# OSHWA_Badges_7.net
KiCad netlist of a schematic drawn in EAGLE
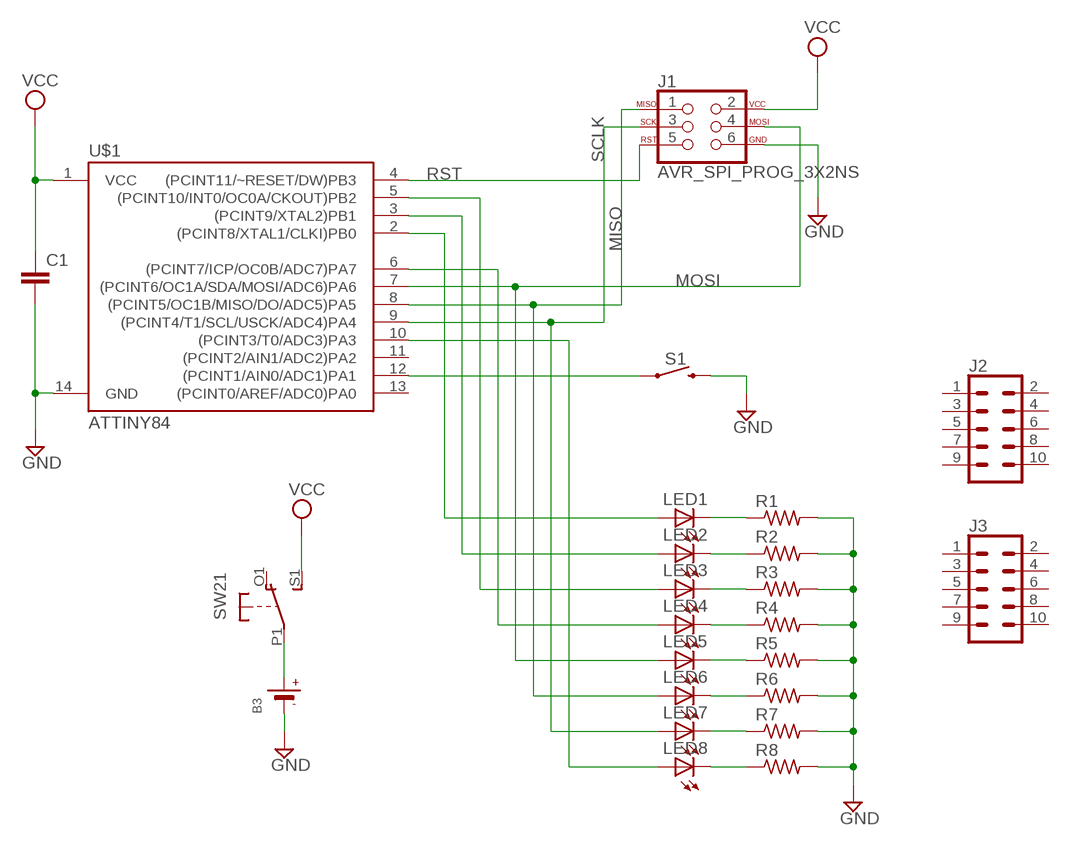
[diagram p0: schematic, sheet 1]

(export (version "E")
  (design (tool "Eeschema 10.0.6"))
  (components
    (comp (ref "B3")
      (value "BATTERYCR2032_BAT-HLD-001")
      (footprint "eagle-import:CR2032_SMT_BAT-HLD-001")
      (libsource (lib "eagle-import") (part "BATTERYCR2032_BAT-HLD-001"))
    )
    (comp (ref "C1")
      (value "C-EUC0805K")
      (footprint "eagle-import:C0805K")
      (libsource (lib "eagle-import") (part "C-EUC0805K"))
    )
    (comp (ref "J1")
      (value "AVR_SPI_PROG_3X2NS")
      (footprint "eagle-import:2X3-NS")
      (libsource (lib "eagle-import") (part "AVR_SPI_PROG_3X2NS"))
    )
    (comp (ref "J2")
      (value "CONN_05X2NO_SILK")
      (footprint "eagle-import:2X5_NOSILK")
      (libsource (lib "eagle-import") (part "CONN_05X2NO_SILK"))
    )
    (comp (ref "J3")
      (value "CONN_05X2NO_SILK")
      (footprint "eagle-import:2X5_NOSILK")
      (libsource (lib "eagle-import") (part "CONN_05X2NO_SILK"))
    )
    (comp (ref "LED1")
      (value "LEDCHIPLED_0805")
      (footprint "eagle-import:CHIPLED_0805")
      (libsource (lib "eagle-import") (part "LEDCHIPLED_0805"))
    )
    (comp (ref "LED2")
      (value "LEDCHIPLED_0805")
      (footprint "eagle-import:CHIPLED_0805")
      (libsource (lib "eagle-import") (part "LEDCHIPLED_0805"))
    )
    (comp (ref "LED3")
      (value "LEDCHIPLED_0805")
      (footprint "eagle-import:CHIPLED_0805")
      (libsource (lib "eagle-import") (part "LEDCHIPLED_0805"))
    )
    (comp (ref "LED4")
      (value "LEDCHIPLED_0805")
      (footprint "eagle-import:CHIPLED_0805")
      (libsource (lib "eagle-import") (part "LEDCHIPLED_0805"))
    )
    (comp (ref "LED5")
      (value "LEDCHIPLED_0805")
      (footprint "eagle-import:CHIPLED_0805")
      (libsource (lib "eagle-import") (part "LEDCHIPLED_0805"))
    )
    (comp (ref "LED6")
      (value "LEDCHIPLED_0805")
      (footprint "eagle-import:CHIPLED_0805")
      (libsource (lib "eagle-import") (part "LEDCHIPLED_0805"))
    )
    (comp (ref "LED7")
      (value "LEDCHIPLED_0805")
      (footprint "eagle-import:CHIPLED_0805")
      (libsource (lib "eagle-import") (part "LEDCHIPLED_0805"))
    )
    (comp (ref "LED8")
      (value "LEDCHIPLED_0805")
      (footprint "eagle-import:CHIPLED_0805")
      (libsource (lib "eagle-import") (part "LEDCHIPLED_0805"))
    )
    (comp (ref "R1")
      (value "R-US_M0805")
      (footprint "eagle-import:M0805")
      (libsource (lib "eagle-import") (part "R-US_M0805"))
    )
    (comp (ref "R2")
      (value "R-US_M0805")
      (footprint "eagle-import:M0805")
      (libsource (lib "eagle-import") (part "R-US_M0805"))
    )
    (comp (ref "R3")
      (value "R-US_M0805")
      (footprint "eagle-import:M0805")
      (libsource (lib "eagle-import") (part "R-US_M0805"))
    )
    (comp (ref "R4")
      (value "R-US_M0805")
      (footprint "eagle-import:M0805")
      (libsource (lib "eagle-import") (part "R-US_M0805"))
    )
    (comp (ref "R5")
      (value "R-US_M0805")
      (footprint "eagle-import:M0805")
      (libsource (lib "eagle-import") (part "R-US_M0805"))
    )
    (comp (ref "R6")
      (value "R-US_M0805")
      (footprint "eagle-import:M0805")
      (libsource (lib "eagle-import") (part "R-US_M0805"))
    )
    (comp (ref "R7")
      (value "R-US_M0805")
      (footprint "eagle-import:M0805")
      (libsource (lib "eagle-import") (part "R-US_M0805"))
    )
    (comp (ref "R8")
      (value "R-US_M0805")
      (footprint "eagle-import:M0805")
      (libsource (lib "eagle-import") (part "R-US_M0805"))
    )
    (comp (ref "S1")
      (value "MOMENTARY-SWITCH-SPST-PTH-6.0MM-KIT")
      (footprint "eagle-import:TACTILE_SWITCH_PTH_6.0MM_KIT")
      (libsource (lib "eagle-import") (part "MOMENTARY-SWITCH-SPST-PTH-6.0MM-KIT"))
    )
    (comp (ref "SW2")
      (value "DPDT-EG1390")
      (footprint "eagle-import:EG1390")
      (libsource (lib "eagle-import") (part "DPDT-EG1390"))
    )
    (comp (ref "U$1")
      (value "ATTINY84")
      (footprint "eagle-import:SO14")
      (libsource (lib "eagle-import") (part "ATTINY84"))
    )
  )
  (nets
    (net (code "1") (name "/MISO") (class "Default")
      (node (ref "J1") (pin "1") (pinfunction "1_1") (pintype "passive"))
      (node (ref "LED6") (pin "A") (pinfunction "A_A") (pintype "passive"))
      (node (ref "U$1") (pin "8") (pinfunction "(PCINT5/OC1B/MISO/DO/ADC5)PA5_8") (pintype "bidirectional"))
    )
    (net (code "2") (name "/MOSI") (class "Default")
      (node (ref "J1") (pin "4") (pinfunction "4_4") (pintype "passive"))
      (node (ref "LED5") (pin "A") (pinfunction "A_A") (pintype "passive"))
      (node (ref "U$1") (pin "7") (pinfunction "(PCINT6/OC1A/SDA/MOSI/ADC6)PA6_7") (pintype "bidirectional"))
    )
    (net (code "3") (name "/RST") (class "Default")
      (node (ref "J1") (pin "5") (pinfunction "5_5") (pintype "passive"))
      (node (ref "U$1") (pin "4") (pinfunction "(PCINT11/~{RESET/DW})PB3_4") (pintype "bidirectional"))
    )
    (net (code "4") (name "/SCLK") (class "Default")
      (node (ref "J1") (pin "3") (pinfunction "3_3") (pintype "passive"))
      (node (ref "LED7") (pin "A") (pinfunction "A_A") (pintype "passive"))
      (node (ref "U$1") (pin "9") (pinfunction "(PCINT4/T1/SCL/USCK/ADC4)PA4_9") (pintype "bidirectional"))
    )
    (net (code "5") (name "GND") (class "Default")
      (node (ref "B3") (pin "-") (pinfunction "-_-") (pintype "passive"))
      (node (ref "C1") (pin "2") (pinfunction "2_2") (pintype "passive"))
      (node (ref "J1") (pin "6") (pinfunction "6_6") (pintype "passive"))
      (node (ref "R1") (pin "2") (pinfunction "2_2") (pintype "passive"))
      (node (ref "R2") (pin "2") (pinfunction "2_2") (pintype "passive"))
      (node (ref "R3") (pin "2") (pinfunction "2_2") (pintype "passive"))
      (node (ref "R4") (pin "2") (pinfunction "2_2") (pintype "passive"))
      (node (ref "R5") (pin "2") (pinfunction "2_2") (pintype "passive"))
      (node (ref "R6") (pin "2") (pinfunction "2_2") (pintype "passive"))
      (node (ref "R7") (pin "2") (pinfunction "2_2") (pintype "passive"))
      (node (ref "R8") (pin "2") (pinfunction "2_2") (pintype "passive"))
      (node (ref "S1") (pin "3") (pinfunction "2_3") (pintype "passive"))
      (node (ref "U$1") (pin "14") (pinfunction "GND_14") (pintype "bidirectional"))
    )
    (net (code "6") (name "Net-(LED1-PadC)") (class "Default")
      (node (ref "LED1") (pin "C") (pinfunction "C_C") (pintype "passive"))
      (node (ref "R1") (pin "1") (pinfunction "1_1") (pintype "passive"))
    )
    (net (code "7") (name "Net-(LED2-PadC)") (class "Default")
      (node (ref "LED2") (pin "C") (pinfunction "C_C") (pintype "passive"))
      (node (ref "R2") (pin "1") (pinfunction "1_1") (pintype "passive"))
    )
    (net (code "8") (name "Net-(LED3-PadC)") (class "Default")
      (node (ref "LED3") (pin "C") (pinfunction "C_C") (pintype "passive"))
      (node (ref "R3") (pin "1") (pinfunction "1_1") (pintype "passive"))
    )
    (net (code "9") (name "Net-(LED4-PadC)") (class "Default")
      (node (ref "LED4") (pin "C") (pinfunction "C_C") (pintype "passive"))
      (node (ref "R4") (pin "1") (pinfunction "1_1") (pintype "passive"))
    )
    (net (code "10") (name "Net-(LED5-PadC)") (class "Default")
      (node (ref "LED5") (pin "C") (pinfunction "C_C") (pintype "passive"))
      (node (ref "R5") (pin "1") (pinfunction "1_1") (pintype "passive"))
    )
    (net (code "11") (name "Net-(LED6-PadC)") (class "Default")
      (node (ref "LED6") (pin "C") (pinfunction "C_C") (pintype "passive"))
      (node (ref "R6") (pin "1") (pinfunction "1_1") (pintype "passive"))
    )
    (net (code "12") (name "Net-(LED7-PadC)") (class "Default")
      (node (ref "LED7") (pin "C") (pinfunction "C_C") (pintype "passive"))
      (node (ref "R7") (pin "1") (pinfunction "1_1") (pintype "passive"))
    )
    (net (code "13") (name "Net-(LED8-PadC)") (class "Default")
      (node (ref "LED8") (pin "C") (pinfunction "C_C") (pintype "passive"))
      (node (ref "R8") (pin "1") (pinfunction "1_1") (pintype "passive"))
    )
    (net (code "14") (name "Net-(SW2A-P)") (class "Default")
      (node (ref "B3") (pin "+$1") (pinfunction "+_+$1") (pintype "passive"))
      (node (ref "B3") (pin "+$2") (pinfunction "+_+$2") (pintype "passive"))
      (node (ref "SW2") (pin "P1") (pinfunction "P_P1") (pintype "passive"))
    )
    (net (code "15") (name "Net-(U$1-(PCINT1{slash}AIN0{slash}ADC1)PA1)") (class "Default")
      (node (ref "S1") (pin "1") (pinfunction "1_1") (pintype "passive"))
      (node (ref "U$1") (pin "12") (pinfunction "(PCINT1/AIN0/ADC1)PA1_12") (pintype "bidirectional"))
    )
    (net (code "16") (name "Net-(U$1-(PCINT3{slash}T0{slash}ADC3)PA3)") (class "Default")
      (node (ref "LED8") (pin "A") (pinfunction "A_A") (pintype "passive"))
      (node (ref "U$1") (pin "10") (pinfunction "(PCINT3/T0/ADC3)PA3_10") (pintype "bidirectional"))
    )
    (net (code "17") (name "Net-(U$1-(PCINT7{slash}ICP{slash}OC0B{slash}ADC7)PA7)") (class "Default")
      (node (ref "LED4") (pin "A") (pinfunction "A_A") (pintype "passive"))
      (node (ref "U$1") (pin "6") (pinfunction "(PCINT7/ICP/OC0B/ADC7)PA7_6") (pintype "bidirectional"))
    )
    (net (code "18") (name "Net-(U$1-(PCINT8{slash}XTAL1{slash}CLKI)PB0)") (class "Default")
      (node (ref "LED1") (pin "A") (pinfunction "A_A") (pintype "passive"))
      (node (ref "U$1") (pin "2") (pinfunction "(PCINT8/XTAL1/CLKI)PB0_2") (pintype "bidirectional"))
    )
    (net (code "19") (name "Net-(U$1-(PCINT9{slash}XTAL2)PB1)") (class "Default")
      (node (ref "LED2") (pin "A") (pinfunction "A_A") (pintype "passive"))
      (node (ref "U$1") (pin "3") (pinfunction "(PCINT9/XTAL2)PB1_3") (pintype "bidirectional"))
    )
    (net (code "20") (name "Net-(U$1-(PCINT10{slash}INT0{slash}OC0A{slash}CKOUT)PB2)") (class "Default")
      (node (ref "LED3") (pin "A") (pinfunction "A_A") (pintype "passive"))
      (node (ref "U$1") (pin "5") (pinfunction "(PCINT10/INT0/OC0A/CKOUT)PB2_5") (pintype "bidirectional"))
    )
    (net (code "21") (name "VCC") (class "Default")
      (node (ref "C1") (pin "1") (pinfunction "1_1") (pintype "passive"))
      (node (ref "J1") (pin "2") (pinfunction "2_2") (pintype "passive"))
      (node (ref "SW2") (pin "S1") (pinfunction "S_S1") (pintype "passive"))
      (node (ref "U$1") (pin "1") (pinfunction "VCC_1") (pintype "bidirectional"))
    )
    (net (code "22") (name "unconnected-(J2-Pad1)") (class "Default")
      (node (ref "J2") (pin "1") (pinfunction "1_1") (pintype "passive"))
    )
    (net (code "23") (name "unconnected-(J2-Pad2)") (class "Default")
      (node (ref "J2") (pin "2") (pinfunction "2_2") (pintype "passive"))
    )
    (net (code "24") (name "unconnected-(J2-Pad3)") (class "Default")
      (node (ref "J2") (pin "3") (pinfunction "3_3") (pintype "passive"))
    )
    (net (code "25") (name "unconnected-(J2-Pad4)") (class "Default")
      (node (ref "J2") (pin "4") (pinfunction "4_4") (pintype "passive"))
    )
    (net (code "26") (name "unconnected-(J2-Pad5)") (class "Default")
      (node (ref "J2") (pin "5") (pinfunction "5_5") (pintype "passive"))
    )
    (net (code "27") (name "unconnected-(J2-Pad6)") (class "Default")
      (node (ref "J2") (pin "6") (pinfunction "6_6") (pintype "passive"))
    )
    (net (code "28") (name "unconnected-(J2-Pad7)") (class "Default")
      (node (ref "J2") (pin "7") (pinfunction "7_7") (pintype "passive"))
    )
    (net (code "29") (name "unconnected-(J2-Pad8)") (class "Default")
      (node (ref "J2") (pin "8") (pinfunction "8_8") (pintype "passive"))
    )
    (net (code "30") (name "unconnected-(J2-Pad9)") (class "Default")
      (node (ref "J2") (pin "9") (pinfunction "9_9") (pintype "passive"))
    )
    (net (code "31") (name "unconnected-(J2-Pad10)") (class "Default")
      (node (ref "J2") (pin "10") (pinfunction "10_10") (pintype "passive"))
    )
    (net (code "32") (name "unconnected-(J3-Pad1)") (class "Default")
      (node (ref "J3") (pin "1") (pinfunction "1_1") (pintype "passive"))
    )
    (net (code "33") (name "unconnected-(J3-Pad2)") (class "Default")
      (node (ref "J3") (pin "2") (pinfunction "2_2") (pintype "passive"))
    )
    (net (code "34") (name "unconnected-(J3-Pad3)") (class "Default")
      (node (ref "J3") (pin "3") (pinfunction "3_3") (pintype "passive"))
    )
    (net (code "35") (name "unconnected-(J3-Pad4)") (class "Default")
      (node (ref "J3") (pin "4") (pinfunction "4_4") (pintype "passive"))
    )
    (net (code "36") (name "unconnected-(J3-Pad5)") (class "Default")
      (node (ref "J3") (pin "5") (pinfunction "5_5") (pintype "passive"))
    )
    (net (code "37") (name "unconnected-(J3-Pad6)") (class "Default")
      (node (ref "J3") (pin "6") (pinfunction "6_6") (pintype "passive"))
    )
    (net (code "38") (name "unconnected-(J3-Pad7)") (class "Default")
      (node (ref "J3") (pin "7") (pinfunction "7_7") (pintype "passive"))
    )
    (net (code "39") (name "unconnected-(J3-Pad8)") (class "Default")
      (node (ref "J3") (pin "8") (pinfunction "8_8") (pintype "passive"))
    )
    (net (code "40") (name "unconnected-(J3-Pad9)") (class "Default")
      (node (ref "J3") (pin "9") (pinfunction "9_9") (pintype "passive"))
    )
    (net (code "41") (name "unconnected-(J3-Pad10)") (class "Default")
      (node (ref "J3") (pin "10") (pinfunction "10_10") (pintype "passive"))
    )
    (net (code "42") (name "unconnected-(SW2A-O-PadO1)") (class "Default")
      (node (ref "SW2") (pin "O1") (pinfunction "O_O1") (pintype "passive"))
    )
    (net (code "43") (name "unconnected-(U$1-(PCINT0{slash}AREF{slash}ADC0)PA0-Pad13)") (class "Default")
      (node (ref "U$1") (pin "13") (pinfunction "(PCINT0/AREF/ADC0)PA0_13") (pintype "bidirectional"))
    )
    (net (code "44") (name "unconnected-(U$1-(PCINT2{slash}AIN1{slash}ADC2)PA2-Pad11)") (class "Default")
      (node (ref "U$1") (pin "11") (pinfunction "(PCINT2/AIN1/ADC2)PA2_11") (pintype "bidirectional"))
    )
  )
)
